# 21_RK3588_CONFIG.net
KiCad netlist of a schematic drawn in Altium Designer
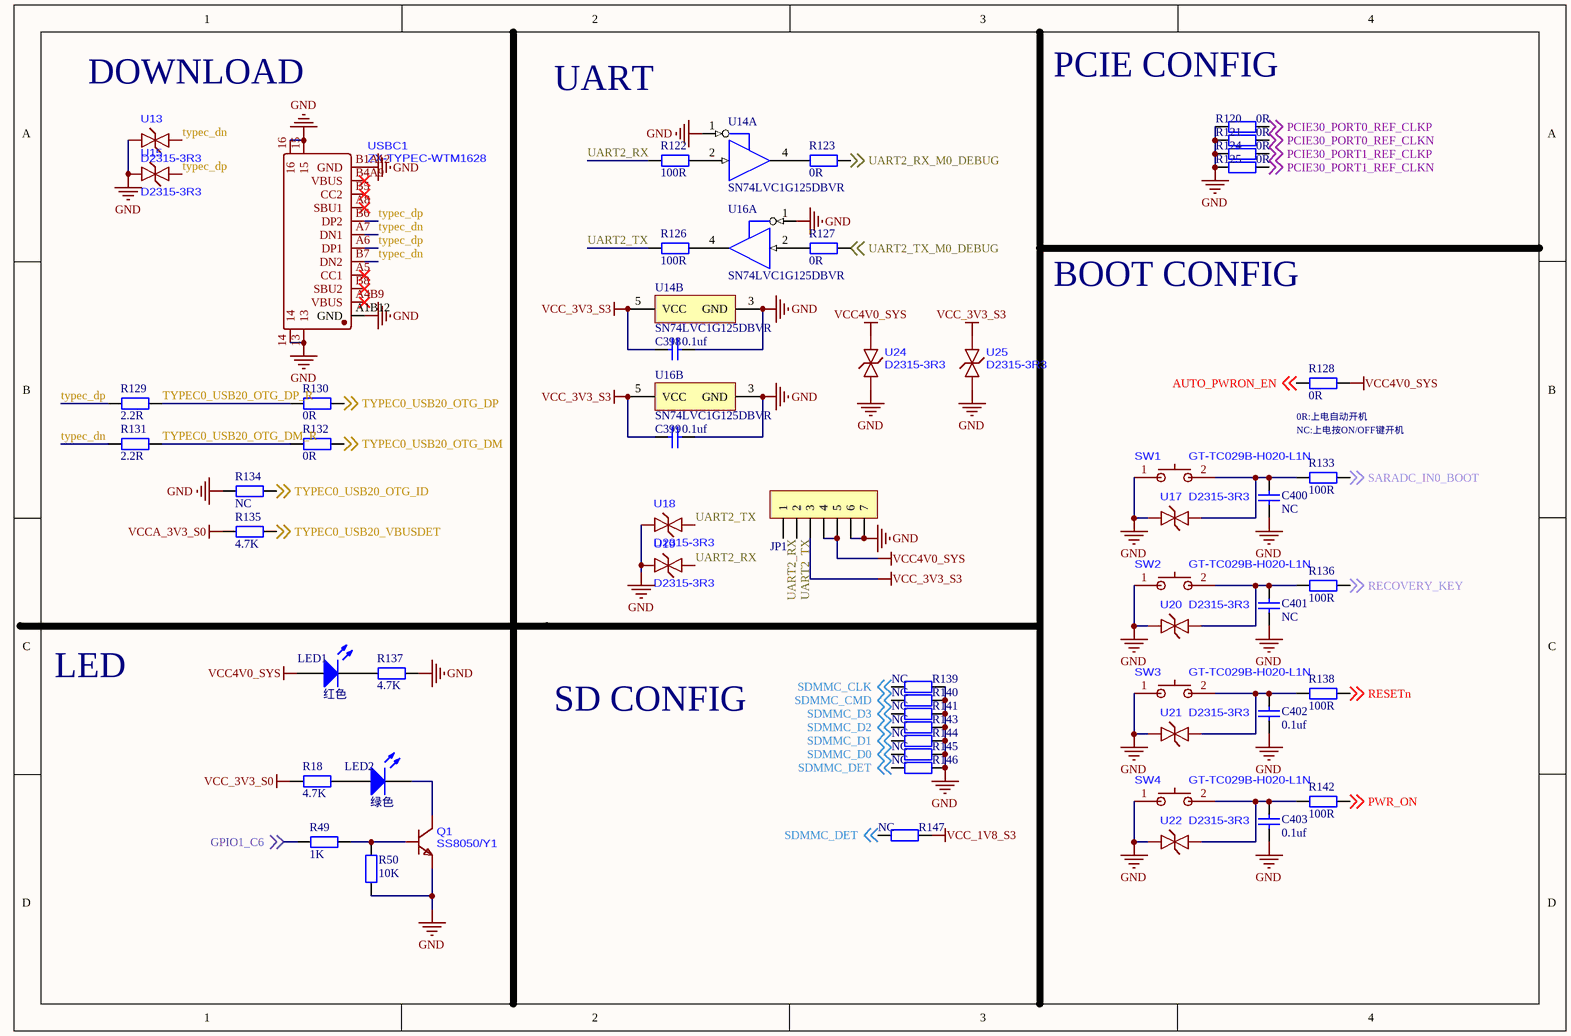
[diagram p0: 21.RK3588_CONFIG.SchDoc]

(export (version "E")
  (design (tool "Eeschema 10.0.6"))
  (components
    (comp (ref "C398")
      (value "0.1uf")
      (footprint "0.PCB1:C0402_L")
      (description "贴片电容/MLCC电容")
      (libsource (lib "RK3588") (part "C"))
    )
    (comp (ref "C399")
      (value "0.1uf")
      (footprint "0.PCB1:C0402_L")
      (description "贴片电容/MLCC电容")
      (libsource (lib "RK3588") (part "C"))
    )
    (comp (ref "C400")
      (value "NC")
      (footprint "0.PCB1:C0402_L")
      (description "贴片电容/MLCC电容")
      (libsource (lib "RK3588") (part "C"))
    )
    (comp (ref "C401")
      (value "NC")
      (footprint "0.PCB1:C0402_L")
      (description "贴片电容/MLCC电容")
      (libsource (lib "RK3588") (part "C"))
    )
    (comp (ref "C402")
      (value "0.1uf")
      (footprint "0.PCB1:C0402_L")
      (description "贴片电容/MLCC电容")
      (libsource (lib "RK3588") (part "C"))
    )
    (comp (ref "C403")
      (value "0.1uf")
      (footprint "0.PCB1:C0402_L")
      (description "贴片电容/MLCC电容")
      (libsource (lib "RK3588") (part "C"))
    )
    (comp (ref "JP1")
      (value "CON-6P")
      (footprint "0.PCB1:SH1.0-WT-7P")
      (description "7P连接器")
      (libsource (lib "RK3588") (part "Header 7"))
    )
    (comp (ref "LED1")
      (value "红色")
      (footprint "0.PCB1:LED0603_R")
      (description "贴片LED")
      (libsource (lib "RK3588") (part "LED"))
    )
    (comp (ref "LED2")
      (value "绿色")
      (footprint "0.PCB1:LED0603_R")
      (description "贴片LED")
      (libsource (lib "RK3588") (part "LED"))
    )
    (comp (ref "Q1")
      (value "SS8050/Y1")
      (footprint "0.PCB1:SOT-23-3_L2.9-W1.3-P1.90-LS2.4-TL")
      (libsource (lib "RK3588") (part "SS8050/Y1"))
    )
    (comp (ref "R18")
      (value "4.7K")
      (footprint "0.PCB1:R0402_L")
      (description "贴片电阻")
      (libsource (lib "RK3588") (part "R"))
    )
    (comp (ref "R49")
      (value "1K")
      (footprint "0.PCB1:R0402_L")
      (description "贴片电阻")
      (libsource (lib "RK3588") (part "R"))
    )
    (comp (ref "R50")
      (value "10K")
      (footprint "0.PCB1:R0402_L")
      (description "贴片电阻")
      (libsource (lib "RK3588") (part "R"))
    )
    (comp (ref "R120")
      (value "0R")
      (footprint "0.PCB1:R0402_L")
      (description "贴片电阻")
      (libsource (lib "RK3588") (part "R"))
    )
    (comp (ref "R121")
      (value "0R")
      (footprint "0.PCB1:R0402_L")
      (description "贴片电阻")
      (libsource (lib "RK3588") (part "R"))
    )
    (comp (ref "R122")
      (value "100R")
      (footprint "0.PCB1:R0402_L")
      (description "贴片电阻")
      (libsource (lib "RK3588") (part "R"))
    )
    (comp (ref "R123")
      (value "0R")
      (footprint "0.PCB1:R0402_L")
      (description "贴片电阻")
      (libsource (lib "RK3588") (part "R"))
    )
    (comp (ref "R124")
      (value "0R")
      (footprint "0.PCB1:R0402_L")
      (description "贴片电阻")
      (libsource (lib "RK3588") (part "R"))
    )
    (comp (ref "R125")
      (value "0R")
      (footprint "0.PCB1:R0402_L")
      (description "贴片电阻")
      (libsource (lib "RK3588") (part "R"))
    )
    (comp (ref "R126")
      (value "100R")
      (footprint "0.PCB1:R0402_L")
      (description "贴片电阻")
      (libsource (lib "RK3588") (part "R"))
    )
    (comp (ref "R127")
      (value "0R")
      (footprint "0.PCB1:R0402_L")
      (description "贴片电阻")
      (libsource (lib "RK3588") (part "R"))
    )
    (comp (ref "R128")
      (value "0R")
      (footprint "0.PCB1:R0402_L")
      (description "贴片电阻")
      (libsource (lib "RK3588") (part "R"))
    )
    (comp (ref "R129")
      (value "2.2R")
      (footprint "0.PCB1:R0402_L")
      (description "贴片电阻")
      (libsource (lib "RK3588") (part "R"))
    )
    (comp (ref "R130")
      (value "0R")
      (footprint "0.PCB1:R0402_L")
      (description "贴片电阻")
      (libsource (lib "RK3588") (part "R"))
    )
    (comp (ref "R131")
      (value "2.2R")
      (footprint "0.PCB1:R0402_L")
      (description "贴片电阻")
      (libsource (lib "RK3588") (part "R"))
    )
    (comp (ref "R132")
      (value "0R")
      (footprint "0.PCB1:R0402_L")
      (description "贴片电阻")
      (libsource (lib "RK3588") (part "R"))
    )
    (comp (ref "R133")
      (value "100R")
      (footprint "0.PCB1:R0402_L")
      (description "贴片电阻")
      (libsource (lib "RK3588") (part "R"))
    )
    (comp (ref "R134")
      (value "NC")
      (footprint "0.PCB1:R0402_L")
      (description "贴片电阻")
      (libsource (lib "RK3588") (part "R"))
    )
    (comp (ref "R135")
      (value "4.7K")
      (footprint "0.PCB1:R0402_L")
      (description "贴片电阻")
      (libsource (lib "RK3588") (part "R"))
    )
    (comp (ref "R136")
      (value "100R")
      (footprint "0.PCB1:R0402_L")
      (description "贴片电阻")
      (libsource (lib "RK3588") (part "R"))
    )
    (comp (ref "R137")
      (value "4.7K")
      (footprint "0.PCB1:R0402_L")
      (description "贴片电阻")
      (libsource (lib "RK3588") (part "R"))
    )
    (comp (ref "R138")
      (value "100R")
      (footprint "0.PCB1:R0402_L")
      (description "贴片电阻")
      (libsource (lib "RK3588") (part "R"))
    )
    (comp (ref "R139")
      (value "NC")
      (footprint "0.PCB1:R0402_L")
      (description "贴片电阻")
      (libsource (lib "RK3588") (part "R"))
    )
    (comp (ref "R140")
      (value "NC")
      (footprint "0.PCB1:R0402_L")
      (description "贴片电阻")
      (libsource (lib "RK3588") (part "R"))
    )
    (comp (ref "R141")
      (value "NC")
      (footprint "0.PCB1:R0402_L")
      (description "贴片电阻")
      (libsource (lib "RK3588") (part "R"))
    )
    (comp (ref "R142")
      (value "100R")
      (footprint "0.PCB1:R0402_L")
      (description "贴片电阻")
      (libsource (lib "RK3588") (part "R"))
    )
    (comp (ref "R143")
      (value "NC")
      (footprint "0.PCB1:R0402_L")
      (description "贴片电阻")
      (libsource (lib "RK3588") (part "R"))
    )
    (comp (ref "R144")
      (value "NC")
      (footprint "0.PCB1:R0402_L")
      (description "贴片电阻")
      (libsource (lib "RK3588") (part "R"))
    )
    (comp (ref "R145")
      (value "NC")
      (footprint "0.PCB1:R0402_L")
      (description "贴片电阻")
      (libsource (lib "RK3588") (part "R"))
    )
    (comp (ref "R146")
      (value "NC")
      (footprint "0.PCB1:R0402_L")
      (description "贴片电阻")
      (libsource (lib "RK3588") (part "R"))
    )
    (comp (ref "R147")
      (value "NC")
      (footprint "0.PCB1:R0402_L")
      (description "贴片电阻")
      (libsource (lib "RK3588") (part "R"))
    )
    (comp (ref "SW1")
      (value "GT-TC029B-H020-L1N")
      (footprint "0.PCB1:SW-SMD_L3.9-W2.9-P4.15-LS5.0")
      (libsource (lib "RK3588") (part "GT-TC029B-H020-L1N"))
    )
    (comp (ref "SW2")
      (value "GT-TC029B-H020-L1N")
      (footprint "0.PCB1:SW-SMD_L3.9-W2.9-P4.15-LS5.0")
      (libsource (lib "RK3588") (part "GT-TC029B-H020-L1N"))
    )
    (comp (ref "SW3")
      (value "GT-TC029B-H020-L1N")
      (footprint "0.PCB1:SW-SMD_L3.9-W2.9-P4.15-LS5.0")
      (libsource (lib "RK3588") (part "GT-TC029B-H020-L1N"))
    )
    (comp (ref "SW4")
      (value "GT-TC029B-H020-L1N")
      (footprint "0.PCB1:SW-SMD_L3.9-W2.9-P4.15-LS5.0")
      (libsource (lib "RK3588") (part "GT-TC029B-H020-L1N"))
    )
    (comp (ref "U13")
      (value "D2315-3R3")
      (footprint "0.PCB1:DFN1006-2L-BI")
      (libsource (lib "RK3588") (part "D2315-3R3"))
    )
    (comp (ref "U14")
      (value "SN74LVC1G125DBVR")
      (footprint "SOT23-5")
      (description "三态输出单路总线缓冲器闸")
      (libsource (lib "") (part "SN74LVC1G125DBVR_1"))
    )
    (comp (ref "U15")
      (value "D2315-3R3")
      (footprint "0.PCB1:DFN1006-2L-BI")
      (libsource (lib "RK3588") (part "D2315-3R3"))
    )
    (comp (ref "U16")
      (value "SN74LVC1G125DBVR")
      (footprint "SOT23-5")
      (description "三态输出单路总线缓冲器闸")
      (libsource (lib "") (part "SN74LVC1G125DBVR_1"))
    )
    (comp (ref "U17")
      (value "D2315-3R3")
      (footprint "0.PCB1:DFN1006-2L-BI")
      (libsource (lib "RK3588") (part "D2315-3R3"))
    )
    (comp (ref "U18")
      (value "D2315-3R3")
      (footprint "0.PCB1:DFN1006-2L-BI")
      (libsource (lib "RK3588") (part "D2315-3R3"))
    )
    (comp (ref "U19")
      (value "D2315-3R3")
      (footprint "0.PCB1:DFN1006-2L-BI")
      (libsource (lib "RK3588") (part "D2315-3R3"))
    )
    (comp (ref "U20")
      (value "D2315-3R3")
      (footprint "0.PCB1:DFN1006-2L-BI")
      (libsource (lib "RK3588") (part "D2315-3R3"))
    )
    (comp (ref "U21")
      (value "D2315-3R3")
      (footprint "0.PCB1:DFN1006-2L-BI")
      (libsource (lib "RK3588") (part "D2315-3R3"))
    )
    (comp (ref "U22")
      (value "D2315-3R3")
      (footprint "0.PCB1:DFN1006-2L-BI")
      (libsource (lib "RK3588") (part "D2315-3R3"))
    )
    (comp (ref "U24")
      (value "D2315-3R3")
      (footprint "0.PCB1:DFN1006-2L-BI")
      (libsource (lib "RK3588") (part "D2315-3R3"))
    )
    (comp (ref "U25")
      (value "D2315-3R3")
      (footprint "0.PCB1:DFN1006-2L-BI")
      (libsource (lib "RK3588") (part "D2315-3R3"))
    )
    (comp (ref "USBC1")
      (value "ZX-TYPEC-WTM1628")
      (footprint "0.PCB1:USB-C-SMD_ZX-TYPEC-WTM1628")
      (libsource (lib "RK3588") (part "ZX-TYPEC-WTM1628"))
    )
  )
  (nets
    (net (code "1") (name "/TYPEC0_USB20_OTG_DM_R") (class "Default")
      (node (ref "R131") (pin "2") (pinfunction "2_2") (pintype "passive"))
      (node (ref "R132") (pin "1") (pinfunction "1_1") (pintype "passive"))
    )
    (net (code "2") (name "/TYPEC0_USB20_OTG_DP_R") (class "Default")
      (node (ref "R129") (pin "2") (pinfunction "2_2") (pintype "passive"))
      (node (ref "R130") (pin "1") (pinfunction "1_1") (pintype "passive"))
    )
    (net (code "3") (name "/UART2_RX") (class "Default")
      (node (ref "JP1") (pin "1") (pinfunction "1_1") (pintype "passive"))
      (node (ref "R122") (pin "1") (pinfunction "1_1") (pintype "passive"))
      (node (ref "U19") (pin "2") (pinfunction "2_2") (pintype "passive"))
    )
    (net (code "4") (name "/UART2_TX") (class "Default")
      (node (ref "JP1") (pin "2") (pinfunction "2_2") (pintype "passive"))
      (node (ref "R126") (pin "1") (pinfunction "1_1") (pintype "passive"))
      (node (ref "U18") (pin "2") (pinfunction "2_2") (pintype "passive"))
    )
    (net (code "5") (name "/typec_dn") (class "Default")
      (node (ref "R131") (pin "1") (pinfunction "1_1") (pintype "passive"))
      (node (ref "U13") (pin "2") (pinfunction "2_2") (pintype "passive"))
      (node (ref "USBC1") (pin "A7") (pinfunction "DN1_A7") (pintype "passive"))
      (node (ref "USBC1") (pin "B7") (pinfunction "DN2_B7") (pintype "passive"))
    )
    (net (code "6") (name "/typec_dp") (class "Default")
      (node (ref "R129") (pin "1") (pinfunction "1_1") (pintype "passive"))
      (node (ref "U15") (pin "2") (pinfunction "2_2") (pintype "passive"))
      (node (ref "USBC1") (pin "A6") (pinfunction "DP1_A6") (pintype "passive"))
      (node (ref "USBC1") (pin "B6") (pinfunction "DP2_B6") (pintype "passive"))
    )
    (net (code "7") (name "AUTO_PWRON_EN") (class "Default")
      (node (ref "R128") (pin "1") (pinfunction "1_1") (pintype "passive"))
    )
    (net (code "8") (name "GND") (class "Default")
      (node (ref "C398") (pin "2") (pinfunction "2_2") (pintype "passive"))
      (node (ref "C399") (pin "2") (pinfunction "2_2") (pintype "passive"))
      (node (ref "C400") (pin "1") (pinfunction "1_1") (pintype "passive"))
      (node (ref "C401") (pin "1") (pinfunction "1_1") (pintype "passive"))
      (node (ref "C402") (pin "1") (pinfunction "1_1") (pintype "passive"))
      (node (ref "C403") (pin "1") (pinfunction "1_1") (pintype "passive"))
      (node (ref "JP1") (pin "6") (pinfunction "6_6") (pintype "passive"))
      (node (ref "JP1") (pin "7") (pinfunction "7_7") (pintype "passive"))
      (node (ref "Q1") (pin "2") (pinfunction "E_2") (pintype "passive"))
      (node (ref "R120") (pin "1") (pinfunction "1_1") (pintype "passive"))
      (node (ref "R121") (pin "1") (pinfunction "1_1") (pintype "passive"))
      (node (ref "R124") (pin "1") (pinfunction "1_1") (pintype "passive"))
      (node (ref "R125") (pin "1") (pinfunction "1_1") (pintype "passive"))
      (node (ref "R134") (pin "1") (pinfunction "1_1") (pintype "passive"))
      (node (ref "R137") (pin "2") (pinfunction "2_2") (pintype "passive"))
      (node (ref "R139") (pin "2") (pinfunction "2_2") (pintype "passive"))
      (node (ref "R140") (pin "2") (pinfunction "2_2") (pintype "passive"))
      (node (ref "R141") (pin "2") (pinfunction "2_2") (pintype "passive"))
      (node (ref "R143") (pin "2") (pinfunction "2_2") (pintype "passive"))
      (node (ref "R144") (pin "2") (pinfunction "2_2") (pintype "passive"))
      (node (ref "R145") (pin "2") (pinfunction "2_2") (pintype "passive"))
      (node (ref "R146") (pin "2") (pinfunction "2_2") (pintype "passive"))
      (node (ref "R50") (pin "1") (pinfunction "1_1") (pintype "passive"))
      (node (ref "SW1") (pin "1") (pinfunction "1_1") (pintype "passive"))
      (node (ref "SW2") (pin "1") (pinfunction "1_1") (pintype "passive"))
      (node (ref "SW3") (pin "1") (pinfunction "1_1") (pintype "passive"))
      (node (ref "SW4") (pin "1") (pinfunction "1_1") (pintype "passive"))
      (node (ref "U13") (pin "1") (pinfunction "1_1") (pintype "passive"))
      (node (ref "U14") (pin "1") (pinfunction "~{OE}_1") (pintype "input"))
      (node (ref "U14") (pin "3") (pinfunction "GND_3") (pintype "power_in"))
      (node (ref "U15") (pin "1") (pinfunction "1_1") (pintype "passive"))
      (node (ref "U16") (pin "1") (pinfunction "~{OE}_1") (pintype "input"))
      (node (ref "U16") (pin "3") (pinfunction "GND_3") (pintype "power_in"))
      (node (ref "U17") (pin "1") (pinfunction "1_1") (pintype "passive"))
      (node (ref "U18") (pin "1") (pinfunction "1_1") (pintype "passive"))
      (node (ref "U19") (pin "1") (pinfunction "1_1") (pintype "passive"))
      (node (ref "U20") (pin "1") (pinfunction "1_1") (pintype "passive"))
      (node (ref "U21") (pin "1") (pinfunction "1_1") (pintype "passive"))
      (node (ref "U22") (pin "1") (pinfunction "1_1") (pintype "passive"))
      (node (ref "U24") (pin "1") (pinfunction "1_1") (pintype "passive"))
      (node (ref "U25") (pin "1") (pinfunction "1_1") (pintype "passive"))
      (node (ref "USBC1") (pin "13") (pinfunction "13_13") (pintype "passive"))
      (node (ref "USBC1") (pin "14") (pinfunction "14_14") (pintype "passive"))
      (node (ref "USBC1") (pin "15") (pinfunction "15_15") (pintype "passive"))
      (node (ref "USBC1") (pin "16") (pinfunction "16_16") (pintype "passive"))
      (node (ref "USBC1") (pin "A1B12") (pinfunction "GND_A1B12") (pintype "passive"))
      (node (ref "USBC1") (pin "B1A12") (pinfunction "GND_B1A12") (pintype "passive"))
    )
    (net (code "9") (name "GPIO1_C6") (class "Default")
      (node (ref "R49") (pin "1") (pinfunction "1_1") (pintype "passive"))
    )
    (net (code "10") (name "Net-(C400-Pad2)") (class "Default")
      (node (ref "C400") (pin "2") (pinfunction "2_2") (pintype "passive"))
      (node (ref "R133") (pin "1") (pinfunction "1_1") (pintype "passive"))
      (node (ref "SW1") (pin "2") (pinfunction "2_2") (pintype "passive"))
      (node (ref "U17") (pin "2") (pinfunction "2_2") (pintype "passive"))
    )
    (net (code "11") (name "Net-(C401-Pad2)") (class "Default")
      (node (ref "C401") (pin "2") (pinfunction "2_2") (pintype "passive"))
      (node (ref "R136") (pin "1") (pinfunction "1_1") (pintype "passive"))
      (node (ref "SW2") (pin "2") (pinfunction "2_2") (pintype "passive"))
      (node (ref "U20") (pin "2") (pinfunction "2_2") (pintype "passive"))
    )
    (net (code "12") (name "Net-(C402-Pad2)") (class "Default")
      (node (ref "C402") (pin "2") (pinfunction "2_2") (pintype "passive"))
      (node (ref "R138") (pin "1") (pinfunction "1_1") (pintype "passive"))
      (node (ref "SW3") (pin "2") (pinfunction "2_2") (pintype "passive"))
      (node (ref "U21") (pin "2") (pinfunction "2_2") (pintype "passive"))
    )
    (net (code "13") (name "Net-(C403-Pad2)") (class "Default")
      (node (ref "C403") (pin "2") (pinfunction "2_2") (pintype "passive"))
      (node (ref "R142") (pin "1") (pinfunction "1_1") (pintype "passive"))
      (node (ref "SW4") (pin "2") (pinfunction "2_2") (pintype "passive"))
      (node (ref "U22") (pin "2") (pinfunction "2_2") (pintype "passive"))
    )
    (net (code "14") (name "Net-(LED1-K)") (class "Default")
      (node (ref "LED1") (pin "2") (pinfunction "K_2") (pintype "passive"))
      (node (ref "R137") (pin "1") (pinfunction "1_1") (pintype "passive"))
    )
    (net (code "15") (name "Net-(LED2-A)") (class "Default")
      (node (ref "LED2") (pin "1") (pinfunction "A_1") (pintype "passive"))
      (node (ref "R18") (pin "2") (pinfunction "2_2") (pintype "passive"))
    )
    (net (code "16") (name "Net-(LED2-K)") (class "Default")
      (node (ref "LED2") (pin "2") (pinfunction "K_2") (pintype "passive"))
      (node (ref "Q1") (pin "3") (pinfunction "C_3") (pintype "passive"))
    )
    (net (code "17") (name "Net-(Q1-B)") (class "Default")
      (node (ref "Q1") (pin "1") (pinfunction "B_1") (pintype "passive"))
      (node (ref "R49") (pin "2") (pinfunction "2_2") (pintype "passive"))
      (node (ref "R50") (pin "2") (pinfunction "2_2") (pintype "passive"))
    )
    (net (code "18") (name "Net-(U14A-A)") (class "Default")
      (node (ref "R122") (pin "2") (pinfunction "2_2") (pintype "passive"))
      (node (ref "U14") (pin "2") (pinfunction "A_2") (pintype "input"))
    )
    (net (code "19") (name "Net-(U14A-Y)") (class "Default")
      (node (ref "R123") (pin "1") (pinfunction "1_1") (pintype "passive"))
      (node (ref "U14") (pin "4") (pinfunction "Y_4") (pintype "tri_state"))
    )
    (net (code "20") (name "Net-(U16A-A)") (class "Default")
      (node (ref "R127") (pin "1") (pinfunction "1_1") (pintype "passive"))
      (node (ref "U16") (pin "2") (pinfunction "A_2") (pintype "input"))
    )
    (net (code "21") (name "Net-(U16A-Y)") (class "Default")
      (node (ref "R126") (pin "2") (pinfunction "2_2") (pintype "passive"))
      (node (ref "U16") (pin "4") (pinfunction "Y_4") (pintype "tri_state"))
    )
    (net (code "22") (name "PCIE30_PORT0_REF_CLKN") (class "Default")
      (node (ref "R121") (pin "2") (pinfunction "2_2") (pintype "passive"))
    )
    (net (code "23") (name "PCIE30_PORT0_REF_CLKP") (class "Default")
      (node (ref "R120") (pin "2") (pinfunction "2_2") (pintype "passive"))
    )
    (net (code "24") (name "PCIE30_PORT1_REF_CLKN") (class "Default")
      (node (ref "R125") (pin "2") (pinfunction "2_2") (pintype "passive"))
    )
    (net (code "25") (name "PCIE30_PORT1_REF_CLKP") (class "Default")
      (node (ref "R124") (pin "2") (pinfunction "2_2") (pintype "passive"))
    )
    (net (code "26") (name "PWR_ON") (class "Default")
      (node (ref "R142") (pin "2") (pinfunction "2_2") (pintype "passive"))
    )
    (net (code "27") (name "RECOVERY_KEY") (class "Default")
      (node (ref "R136") (pin "2") (pinfunction "2_2") (pintype "passive"))
    )
    (net (code "28") (name "RESETn") (class "Default")
      (node (ref "R138") (pin "2") (pinfunction "2_2") (pintype "passive"))
    )
    (net (code "29") (name "SARADC_IN0_BOOT") (class "Default")
      (node (ref "R133") (pin "2") (pinfunction "2_2") (pintype "passive"))
    )
    (net (code "30") (name "SDMMC_CLK") (class "Default")
      (node (ref "R139") (pin "1") (pinfunction "1_1") (pintype "passive"))
    )
    (net (code "31") (name "SDMMC_CMD") (class "Default")
      (node (ref "R140") (pin "1") (pinfunction "1_1") (pintype "passive"))
    )
    (net (code "32") (name "SDMMC_D0") (class "Default")
      (node (ref "R145") (pin "1") (pinfunction "1_1") (pintype "passive"))
    )
    (net (code "33") (name "SDMMC_D1") (class "Default")
      (node (ref "R144") (pin "1") (pinfunction "1_1") (pintype "passive"))
    )
    (net (code "34") (name "SDMMC_D2") (class "Default")
      (node (ref "R143") (pin "1") (pinfunction "1_1") (pintype "passive"))
    )
    (net (code "35") (name "SDMMC_D3") (class "Default")
      (node (ref "R141") (pin "1") (pinfunction "1_1") (pintype "passive"))
    )
    (net (code "36") (name "SDMMC_DET") (class "Default")
      (node (ref "R146") (pin "1") (pinfunction "1_1") (pintype "passive"))
      (node (ref "R147") (pin "1") (pinfunction "1_1") (pintype "passive"))
    )
    (net (code "37") (name "TYPEC0_USB20_OTG_DM") (class "Default")
      (node (ref "R132") (pin "2") (pinfunction "2_2") (pintype "passive"))
    )
    (net (code "38") (name "TYPEC0_USB20_OTG_DP") (class "Default")
      (node (ref "R130") (pin "2") (pinfunction "2_2") (pintype "passive"))
    )
    (net (code "39") (name "TYPEC0_USB20_OTG_ID") (class "Default")
      (node (ref "R134") (pin "2") (pinfunction "2_2") (pintype "passive"))
    )
    (net (code "40") (name "TYPEC0_USB20_VBUSDET") (class "Default")
      (node (ref "R135") (pin "2") (pinfunction "2_2") (pintype "passive"))
    )
    (net (code "41") (name "UART2_RX_M0_DEBUG") (class "Default")
      (node (ref "R123") (pin "2") (pinfunction "2_2") (pintype "passive"))
    )
    (net (code "42") (name "UART2_TX_M0_DEBUG") (class "Default")
      (node (ref "R127") (pin "2") (pinfunction "2_2") (pintype "passive"))
    )
    (net (code "43") (name "VCC4V0_SYS") (class "Default")
      (node (ref "JP1") (pin "4") (pinfunction "4_4") (pintype "passive"))
      (node (ref "JP1") (pin "5") (pinfunction "5_5") (pintype "passive"))
      (node (ref "LED1") (pin "1") (pinfunction "A_1") (pintype "passive"))
      (node (ref "R128") (pin "2") (pinfunction "2_2") (pintype "passive"))
      (node (ref "U24") (pin "2") (pinfunction "2_2") (pintype "passive"))
    )
    (net (code "44") (name "VCCA_3V3_S0") (class "Default")
      (node (ref "R135") (pin "1") (pinfunction "1_1") (pintype "passive"))
    )
    (net (code "45") (name "VCC_1V8_S3") (class "Default")
      (node (ref "R147") (pin "2") (pinfunction "2_2") (pintype "passive"))
    )
    (net (code "46") (name "VCC_3V3_S0") (class "Default")
      (node (ref "R18") (pin "1") (pinfunction "1_1") (pintype "passive"))
    )
    (net (code "47") (name "VCC_3V3_S3") (class "Default")
      (node (ref "C398") (pin "1") (pinfunction "1_1") (pintype "passive"))
      (node (ref "C399") (pin "1") (pinfunction "1_1") (pintype "passive"))
      (node (ref "JP1") (pin "3") (pinfunction "3_3") (pintype "passive"))
      (node (ref "U14") (pin "5") (pinfunction "VCC_5") (pintype "power_in"))
      (node (ref "U16") (pin "5") (pinfunction "VCC_5") (pintype "power_in"))
      (node (ref "U25") (pin "2") (pinfunction "2_2") (pintype "passive"))
    )
    (net (code "48") (name "unconnected-(USBC1-CC1-PadA5)") (class "Default")
      (node (ref "USBC1") (pin "A5") (pinfunction "CC1_A5") (pintype "passive+no_connect"))
    )
    (net (code "49") (name "unconnected-(USBC1-CC2-PadB5)") (class "Default")
      (node (ref "USBC1") (pin "B5") (pinfunction "CC2_B5") (pintype "passive+no_connect"))
    )
    (net (code "50") (name "unconnected-(USBC1-SBU1-PadA8)") (class "Default")
      (node (ref "USBC1") (pin "A8") (pinfunction "SBU1_A8") (pintype "passive+no_connect"))
    )
    (net (code "51") (name "unconnected-(USBC1-SBU2-PadB8)") (class "Default")
      (node (ref "USBC1") (pin "B8") (pinfunction "SBU2_B8") (pintype "passive+no_connect"))
    )
    (net (code "52") (name "unconnected-(USBC1-VBUS-PadA4B9)") (class "Default")
      (node (ref "USBC1") (pin "A4B9") (pinfunction "VBUS_A4B9") (pintype "passive+no_connect"))
    )
    (net (code "53") (name "unconnected-(USBC1-VBUS-PadB4A9)") (class "Default")
      (node (ref "USBC1") (pin "B4A9") (pinfunction "VBUS_B4A9") (pintype "passive+no_connect"))
    )
  )
)
